# BS4C_00006_03_EasyEDA.net
KiCad netlist of a schematic drawn in EasyEDA Pro
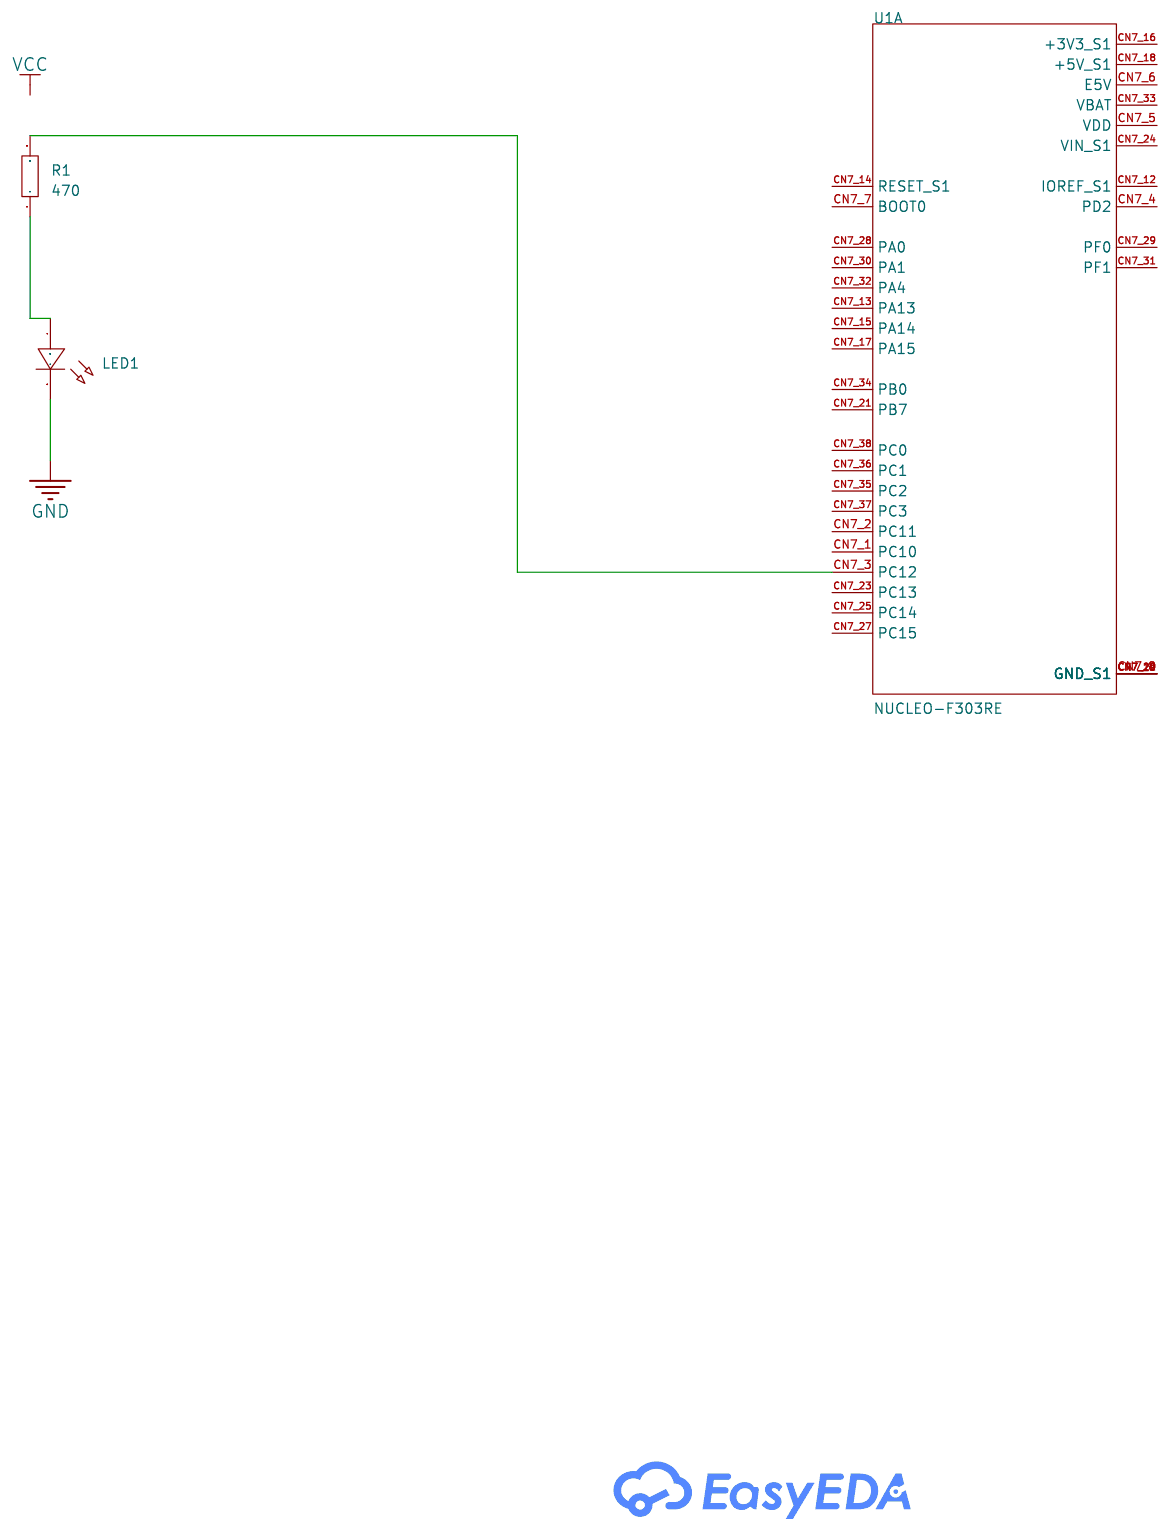
[diagram p0: schematic sheet]

(export (version "E")
  (design (tool "Eeschema 10.0.6"))
  (components
    (comp (ref "LED1")
      (value "~")
      (footprint "easyedapro:LED-TH_BD3.0-P2.54-FD")
      (libsource (lib "easyedapro") (part "LED_TH-R"))
    )
    (comp (ref "R1") (value "470") (footprint "easyedapro:R1210") (libsource (lib "easyedapro") (part "Res")))
    (comp (ref "U1") (value "NUCLEO-F303RE") (libsource (lib "easyedapro") (part "NUCLEO-F303RE")))
  )
  (nets
    (net (code "1") (name "GND") (class "Default")
      (node (ref "LED1") (pin "2") (pinfunction "A_2") (pintype "input"))
    )
    (net (code "2") (name "Net-(LED1-C)") (class "Default")
      (node (ref "LED1") (pin "1") (pinfunction "C_1") (pintype "input"))
      (node (ref "R1") (pin "1") (pinfunction "1_1") (pintype "input"))
    )
    (net (code "3") (name "Net-(U1A-GND_S1-PadCN7_19)") (class "Default")
      (node (ref "U1") (pin "CN7_19") (pinfunction "GND_S1_CN7_19") (pintype "unspecified"))
      (node (ref "U1") (pin "CN7_20") (pinfunction "GND_S1_CN7_20") (pintype "unspecified"))
      (node (ref "U1") (pin "CN7_22") (pinfunction "GND_S1_CN7_22") (pintype "unspecified"))
      (node (ref "U1") (pin "CN7_8") (pinfunction "GND_S1_CN7_8") (pintype "unspecified"))
    )
    (net (code "4") (name "Net-(U1A-PC12)") (class "Default")
      (node (ref "R1") (pin "2") (pinfunction "2_2") (pintype "input"))
      (node (ref "U1") (pin "CN7_3") (pinfunction "PC12_CN7_3") (pintype "bidirectional"))
    )
    (net (code "6") (name "unconnected-(U1A-+3V3_S1-PadCN7_16)") (class "Default")
      (node (ref "U1") (pin "CN7_16") (pinfunction "+3V3_S1_CN7_16") (pintype "unspecified"))
    )
    (net (code "7") (name "unconnected-(U1A-+5V_S1-PadCN7_18)") (class "Default")
      (node (ref "U1") (pin "CN7_18") (pinfunction "+5V_S1_CN7_18") (pintype "unspecified"))
    )
    (net (code "8") (name "unconnected-(U1A-BOOT0-PadCN7_7)") (class "Default")
      (node (ref "U1") (pin "CN7_7") (pinfunction "BOOT0_CN7_7") (pintype "bidirectional"))
    )
    (net (code "9") (name "unconnected-(U1A-E5V-PadCN7_6)") (class "Default")
      (node (ref "U1") (pin "CN7_6") (pinfunction "E5V_CN7_6") (pintype "unspecified"))
    )
    (net (code "10") (name "unconnected-(U1A-IOREF_S1-PadCN7_12)") (class "Default")
      (node (ref "U1") (pin "CN7_12") (pinfunction "IOREF_S1_CN7_12") (pintype "bidirectional"))
    )
    (net (code "11") (name "unconnected-(U1A-PA0-PadCN7_28)") (class "Default")
      (node (ref "U1") (pin "CN7_28") (pinfunction "PA0_CN7_28") (pintype "bidirectional"))
    )
    (net (code "12") (name "unconnected-(U1A-PA1-PadCN7_30)") (class "Default")
      (node (ref "U1") (pin "CN7_30") (pinfunction "PA1_CN7_30") (pintype "bidirectional"))
    )
    (net (code "13") (name "unconnected-(U1A-PA4-PadCN7_32)") (class "Default")
      (node (ref "U1") (pin "CN7_32") (pinfunction "PA4_CN7_32") (pintype "bidirectional"))
    )
    (net (code "14") (name "unconnected-(U1A-PA13-PadCN7_13)") (class "Default")
      (node (ref "U1") (pin "CN7_13") (pinfunction "PA13_CN7_13") (pintype "bidirectional"))
    )
    (net (code "15") (name "unconnected-(U1A-PA14-PadCN7_15)") (class "Default")
      (node (ref "U1") (pin "CN7_15") (pinfunction "PA14_CN7_15") (pintype "bidirectional"))
    )
    (net (code "16") (name "unconnected-(U1A-PA15-PadCN7_17)") (class "Default")
      (node (ref "U1") (pin "CN7_17") (pinfunction "PA15_CN7_17") (pintype "bidirectional"))
    )
    (net (code "17") (name "unconnected-(U1A-PB0-PadCN7_34)") (class "Default")
      (node (ref "U1") (pin "CN7_34") (pinfunction "PB0_CN7_34") (pintype "bidirectional"))
    )
    (net (code "18") (name "unconnected-(U1A-PB7-PadCN7_21)") (class "Default")
      (node (ref "U1") (pin "CN7_21") (pinfunction "PB7_CN7_21") (pintype "bidirectional"))
    )
    (net (code "19") (name "unconnected-(U1A-PC0-PadCN7_38)") (class "Default")
      (node (ref "U1") (pin "CN7_38") (pinfunction "PC0_CN7_38") (pintype "bidirectional"))
    )
    (net (code "20") (name "unconnected-(U1A-PC1-PadCN7_36)") (class "Default")
      (node (ref "U1") (pin "CN7_36") (pinfunction "PC1_CN7_36") (pintype "bidirectional"))
    )
    (net (code "21") (name "unconnected-(U1A-PC2-PadCN7_35)") (class "Default")
      (node (ref "U1") (pin "CN7_35") (pinfunction "PC2_CN7_35") (pintype "bidirectional"))
    )
    (net (code "22") (name "unconnected-(U1A-PC3-PadCN7_37)") (class "Default")
      (node (ref "U1") (pin "CN7_37") (pinfunction "PC3_CN7_37") (pintype "bidirectional"))
    )
    (net (code "23") (name "unconnected-(U1A-PC10-PadCN7_1)") (class "Default")
      (node (ref "U1") (pin "CN7_1") (pinfunction "PC10_CN7_1") (pintype "bidirectional"))
    )
    (net (code "24") (name "unconnected-(U1A-PC11-PadCN7_2)") (class "Default")
      (node (ref "U1") (pin "CN7_2") (pinfunction "PC11_CN7_2") (pintype "bidirectional"))
    )
    (net (code "25") (name "unconnected-(U1A-PC13-PadCN7_23)") (class "Default")
      (node (ref "U1") (pin "CN7_23") (pinfunction "PC13_CN7_23") (pintype "bidirectional"))
    )
    (net (code "26") (name "unconnected-(U1A-PC14-PadCN7_25)") (class "Default")
      (node (ref "U1") (pin "CN7_25") (pinfunction "PC14_CN7_25") (pintype "bidirectional"))
    )
    (net (code "27") (name "unconnected-(U1A-PC15-PadCN7_27)") (class "Default")
      (node (ref "U1") (pin "CN7_27") (pinfunction "PC15_CN7_27") (pintype "bidirectional"))
    )
    (net (code "28") (name "unconnected-(U1A-PD2-PadCN7_4)") (class "Default")
      (node (ref "U1") (pin "CN7_4") (pinfunction "PD2_CN7_4") (pintype "bidirectional"))
    )
    (net (code "29") (name "unconnected-(U1A-PF0-PadCN7_29)") (class "Default")
      (node (ref "U1") (pin "CN7_29") (pinfunction "PF0_CN7_29") (pintype "bidirectional"))
    )
    (net (code "30") (name "unconnected-(U1A-PF1-PadCN7_31)") (class "Default")
      (node (ref "U1") (pin "CN7_31") (pinfunction "PF1_CN7_31") (pintype "bidirectional"))
    )
    (net (code "31") (name "unconnected-(U1A-RESET_S1-PadCN7_14)") (class "Default")
      (node (ref "U1") (pin "CN7_14") (pinfunction "RESET_S1_CN7_14") (pintype "bidirectional"))
    )
    (net (code "32") (name "unconnected-(U1A-VBAT-PadCN7_33)") (class "Default")
      (node (ref "U1") (pin "CN7_33") (pinfunction "VBAT_CN7_33") (pintype "unspecified"))
    )
    (net (code "33") (name "unconnected-(U1A-VDD-PadCN7_5)") (class "Default")
      (node (ref "U1") (pin "CN7_5") (pinfunction "VDD_CN7_5") (pintype "unspecified"))
    )
    (net (code "34") (name "unconnected-(U1A-VIN_S1-PadCN7_24)") (class "Default")
      (node (ref "U1") (pin "CN7_24") (pinfunction "VIN_S1_CN7_24") (pintype "unspecified"))
    )
  )
)
